# 18_HD4_PUMP_2.net
KiCad netlist of a schematic drawn in Altium Designer
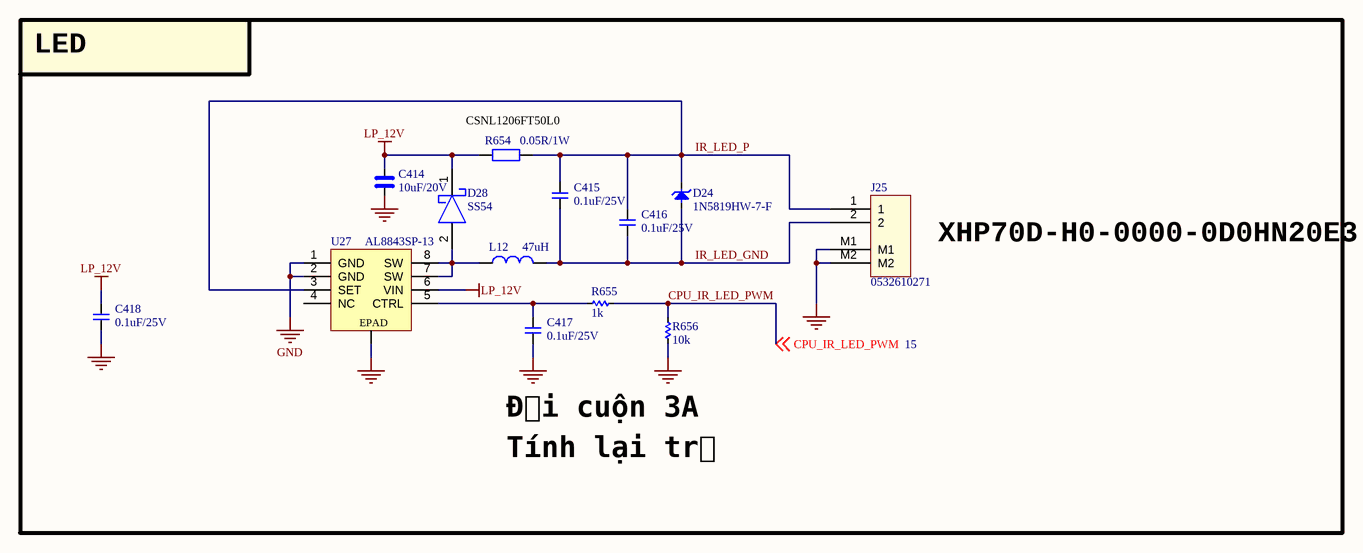
[diagram p0: 18_HD4_PUMP_2.SchDoc]

(export (version "E")
  (design (tool "Eeschema 10.0.6"))
  (components
    (comp (ref "C414")
      (value "10uF/20V")
      (footprint "CAP_C_2012X110")
      (description "CAP High Value")
      (libsource (lib "LABLIB") (part "_CAP_C_High_2"))
    )
    (comp (ref "C415")
      (value "0.1uF/25V")
      (footprint "CAP_C_1608X80")
      (description "CAP")
      (libsource (lib "LABLIB") (part "_CAP_C_2"))
    )
    (comp (ref "C416")
      (value "0.1uF/25V")
      (footprint "CAP_C_1608X80")
      (description "CAP")
      (libsource (lib "LABLIB") (part "_CAP_C_2"))
    )
    (comp (ref "C417")
      (value "0.1uF/25V")
      (footprint "CAP_C_1608X80")
      (description "CAP")
      (libsource (lib "LABLIB") (part "_CAP_C_2"))
    )
    (comp (ref "C418")
      (value "0.1uF/25V")
      (footprint "CAP_C_1608X80")
      (description "CAP")
      (libsource (lib "LABLIB") (part "_CAP_C_2"))
    )
    (comp (ref "D24")
      (value "1N5819HW-7-F")
      (footprint "SOD3717X145N")
      (description "Zenner")
      (libsource (lib "LABLIB") (part "DIODE Zener"))
    )
    (comp (ref "D28")
      (value "SS54")
      (footprint "DO-214AC_SMA")
      (description "DIODE SCHOTTKY 60V 3A DO214AA")
      (libsource (lib "EXP_HW_V3") (part "SS54"))
    )
    (comp (ref "J25")
      (value "0532610271")
      (footprint "MOLEX_5040500291")
      (libsource (lib "LABLIB") (part "Header 2x1_2M"))
    )
    (comp (ref "L12")
      (value "47uH")
      (footprint "IND_MP_1250x1250x850")
      (description "B82477P4473M000")
      (fields
        (field (name "PARTNO") "78477010")
        (field (name "MANUFACTURER") "Wurth Elektronik")
        (field (name "CREATED BY") "Baojun Chen")
      )
      (libsource (lib "EXP_HW_V3") (part "L-SMD-1"))
    )
    (comp (ref "R654")
      (value "0.05R/1W")
      (footprint "RES_C_3216X70")
      (description "RES")
      (libsource (lib "LABLIB") (part "_RES"))
    )
    (comp (ref "R655")
      (value "1k")
      (footprint "RES_C_1608X60")
      (description "RES")
      (libsource (lib "LABLIB") (part "_RES_B_2"))
    )
    (comp (ref "R656")
      (value "10k")
      (footprint "RES_C_1608X60")
      (description "RES")
      (libsource (lib "LABLIB") (part "_RES_B_2"))
    )
    (comp (ref "U27")
      (value "AL8843SP-13")
      (footprint "SOIC127P602X173-8N_EPAD")
      (description "IC LED DRIVER RGLTR PWM 3A 8SO")
      (libsource (lib "EXP_HW_V3") (part "AL8843SP-13"))
    )
  )
  (nets
    (net (code "1") (name "/IR_LED_GND") (class "Default")
      (node (ref "C415") (pin "1") (pinfunction "1_1") (pintype "passive"))
      (node (ref "C416") (pin "1") (pinfunction "1_1") (pintype "passive"))
      (node (ref "D24") (pin "2") (pinfunction "A_2") (pintype "passive"))
      (node (ref "J25") (pin "2") (pinfunction "2_2") (pintype "passive"))
      (node (ref "L12") (pin "2") (pinfunction "2_2") (pintype "passive"))
    )
    (net (code "2") (name "/IR_LED_P") (class "Default")
      (node (ref "C415") (pin "2") (pinfunction "2_2") (pintype "passive"))
      (node (ref "C416") (pin "2") (pinfunction "2_2") (pintype "passive"))
      (node (ref "D24") (pin "1") (pinfunction "K_1") (pintype "passive"))
      (node (ref "J25") (pin "1") (pinfunction "1_1") (pintype "passive"))
      (node (ref "R654") (pin "2") (pinfunction "2_2") (pintype "passive"))
      (node (ref "U27") (pin "3") (pinfunction "SET_3") (pintype "passive"))
    )
    (net (code "3") (name "CPU_IR_LED_PWM") (class "Default")
      (node (ref "R655") (pin "2") (pinfunction "2_2") (pintype "passive"))
      (node (ref "R656") (pin "1") (pinfunction "1_1") (pintype "passive"))
    )
    (net (code "4") (name "GND") (class "Default")
      (node (ref "C414") (pin "2") (pinfunction "2_2") (pintype "passive"))
      (node (ref "C417") (pin "1") (pinfunction "1_1") (pintype "passive"))
      (node (ref "C418") (pin "1") (pinfunction "1_1") (pintype "passive"))
      (node (ref "J25") (pin "M1") (pinfunction "M1_M1") (pintype "passive"))
      (node (ref "J25") (pin "M2") (pinfunction "M2_M2") (pintype "passive"))
      (node (ref "R656") (pin "2") (pinfunction "2_2") (pintype "passive"))
      (node (ref "U27") (pin "1") (pinfunction "GND_1") (pintype "passive"))
      (node (ref "U27") (pin "2") (pinfunction "GND_2") (pintype "passive"))
      (node (ref "U27") (pin "9") (pinfunction "EPAD_9") (pintype "passive"))
    )
    (net (code "5") (name "LP_12V") (class "Default")
      (node (ref "C414") (pin "1") (pinfunction "1_1") (pintype "passive"))
      (node (ref "C418") (pin "2") (pinfunction "2_2") (pintype "passive"))
      (node (ref "D28") (pin "1") (pinfunction "1_1") (pintype "passive"))
      (node (ref "R654") (pin "1") (pinfunction "1_1") (pintype "passive"))
      (node (ref "U27") (pin "6") (pinfunction "VIN_6") (pintype "passive"))
    )
    (net (code "6") (name "Net-(D28-Pad2)") (class "Default")
      (node (ref "D28") (pin "2") (pinfunction "2_2") (pintype "passive"))
      (node (ref "L12") (pin "1") (pinfunction "1_1") (pintype "passive"))
      (node (ref "U27") (pin "7") (pinfunction "SW_7") (pintype "passive"))
      (node (ref "U27") (pin "8") (pinfunction "SW_8") (pintype "passive"))
    )
    (net (code "7") (name "Net-(U27-CTRL)") (class "Default")
      (node (ref "C417") (pin "2") (pinfunction "2_2") (pintype "passive"))
      (node (ref "R655") (pin "1") (pinfunction "1_1") (pintype "passive"))
      (node (ref "U27") (pin "5") (pinfunction "CTRL_5") (pintype "passive"))
    )
    (net (code "8") (name "unconnected-(U27-NC-Pad4)") (class "Default")
      (node (ref "U27") (pin "4") (pinfunction "NC_4") (pintype "passive"))
    )
  )
)
